# EasyEDA_Schematic_V2_0.net
KiCad netlist of a schematic drawn in EasyEDA
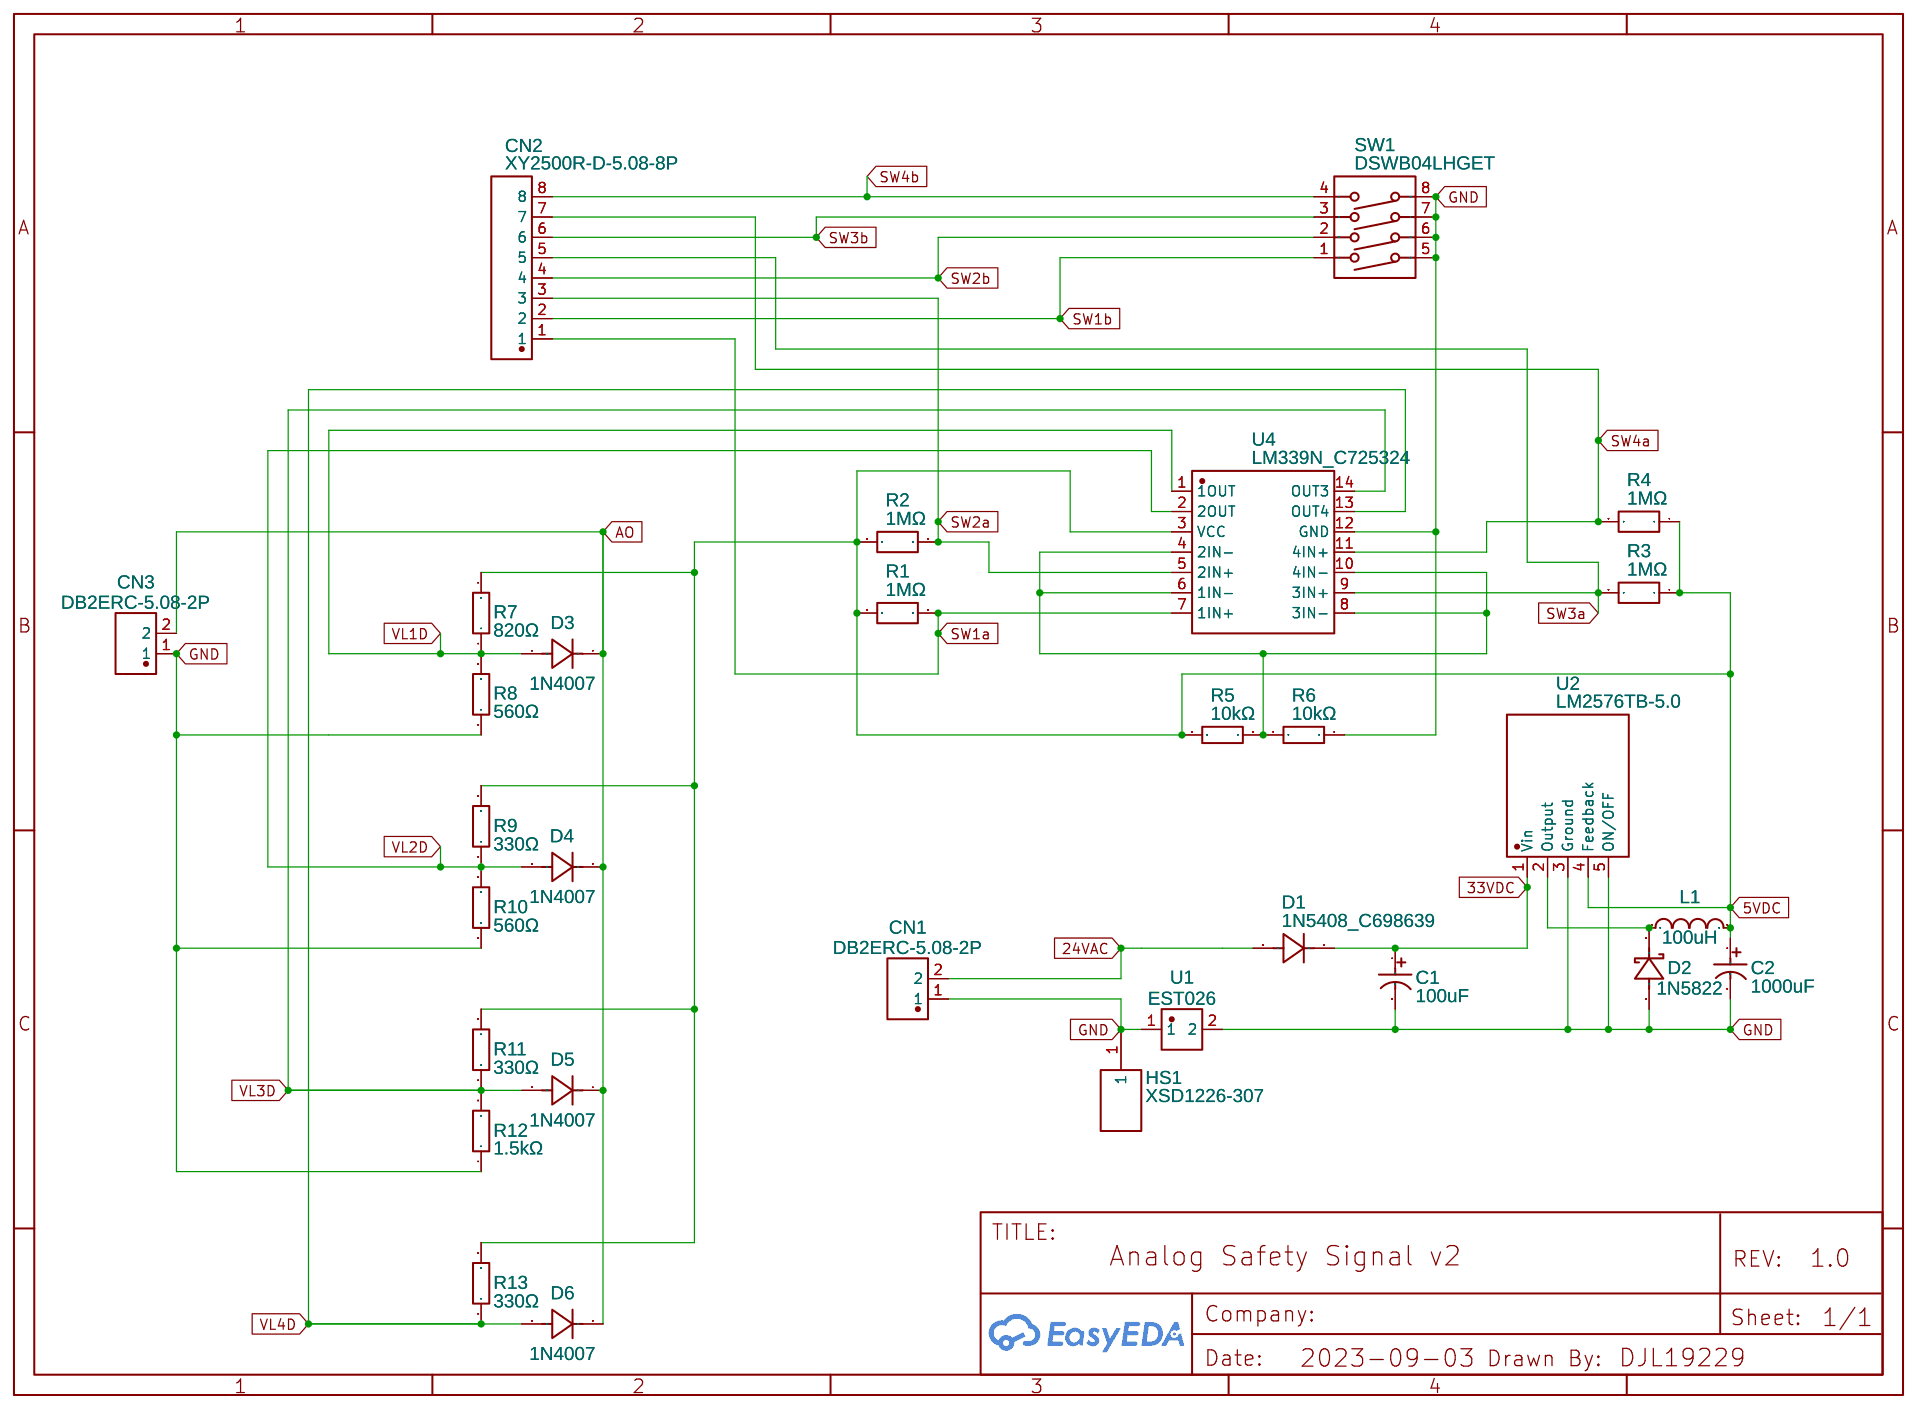
[diagram p0: schematic sheet]

(export (version "E")
  (design (tool "Eeschema 10.0.6"))
  (components
    (comp (ref "C1")
      (value "100uF")
      (fields
        (field (name "Manufacturer Part") "GR107M050F12RR0VH4FP0")
        (field (name "Manufacturer") "CX(承兴)")
      )
      (libsource (lib "") (part "100uF 50V 8*12Black high frequency"))
    )
    (comp (ref "C2")
      (value "1000uF")
      (fields
        (field (name "Manufacturer Part") "35YXJ1000M12.5X20")
        (field (name "Manufacturer") "rubycon(红宝石)")
      )
      (libsource (lib "") (part "35YXJ1000M12.5X20"))
    )
    (comp (ref "CN1")
      (value "DB2ERC-5.08-2P")
      (fields
        (field (name "Manufacturer Part") "DB2ERC-5.08-2P-GN")
        (field (name "Manufacturer") "DIBO(地博电气)")
      )
      (libsource (lib "") (part "DB2ERC-5.08-2P"))
    )
    (comp (ref "CN2")
      (value "XY2500R-D-5.08-8P")
      (fields (field (name "Manufacturer") "XINLAIYA(新莱亚)"))
      (libsource (lib "") (part "XY2500R-D-5.08-8P"))
    )
    (comp (ref "CN3")
      (value "DB2ERC-5.08-2P")
      (fields
        (field (name "Manufacturer Part") "DB2ERC-5.08-2P-GN")
        (field (name "Manufacturer") "DIBO(地博电气)")
      )
      (libsource (lib "") (part "DB2ERC-5.08-2P"))
    )
    (comp (ref "D1")
      (value "1N5408_C698639")
      (fields (field (name "Manufacturer Part") "1N5408") (field (name "Manufacturer") "YANGJIE(扬杰)"))
      (libsource (lib "") (part "1N5408_C698639"))
    )
    (comp (ref "D2")
      (value "1N5822")
      (fields (field (name "Manufacturer") "FUXINSEMI(富芯森美)"))
      (libsource (lib "") (part "1N5822_C3018526"))
    )
    (comp (ref "D3")
      (value "1N4007")
      (fields (field (name "Manufacturer") "YANGJIE(扬杰)"))
      (libsource (lib "") (part "1N4007_C2986225"))
    )
    (comp (ref "D4")
      (value "1N4007")
      (fields (field (name "Manufacturer") "YANGJIE(扬杰)"))
      (libsource (lib "") (part "1N4007_C2986225"))
    )
    (comp (ref "D5")
      (value "1N4007")
      (fields (field (name "Manufacturer") "YANGJIE(扬杰)"))
      (libsource (lib "") (part "1N4007_C2986225"))
    )
    (comp (ref "D6")
      (value "1N4007")
      (fields (field (name "Manufacturer") "YANGJIE(扬杰)"))
      (libsource (lib "") (part "1N4007_C2986225"))
    )
    (comp (ref "HS1")
      (value "XSD1226-307")
      (fields (field (name "Manufacturer") "XSD(鑫顺达)"))
      (libsource (lib "") (part "XSD1226-307"))
    )
    (comp (ref "L1")
      (value "100uH")
      (fields (field (name "Manufacturer Part") "VLU0810-101K") (field (name "Manufacturer") "FH(风华)"))
      (libsource (lib "") (part "VLU0810-101K"))
    )
    (comp (ref "R1")
      (value "1MΩ")
      (fields
        (field (name "Manufacturer Part") "MF1/4W-1MΩ±1%T52")
        (field (name "Manufacturer") "Huaxing Mechanical-Elec.")
      )
      (libsource (lib "") (part "MF1/4W-1MΩ±1%T52"))
    )
    (comp (ref "R2")
      (value "1MΩ")
      (fields
        (field (name "Manufacturer Part") "MF1/4W-1MΩ±1%T52")
        (field (name "Manufacturer") "Huaxing Mechanical-Elec.")
      )
      (libsource (lib "") (part "MF1/4W-1MΩ±1%T52"))
    )
    (comp (ref "R3")
      (value "1MΩ")
      (fields
        (field (name "Manufacturer Part") "MF1/4W-1MΩ±1%T52")
        (field (name "Manufacturer") "Huaxing Mechanical-Elec.")
      )
      (libsource (lib "") (part "MF1/4W-1MΩ±1%T52"))
    )
    (comp (ref "R4")
      (value "1MΩ")
      (fields
        (field (name "Manufacturer Part") "MF1/4W-1MΩ±1%T52")
        (field (name "Manufacturer") "Huaxing Mechanical-Elec.")
      )
      (libsource (lib "") (part "MF1/4W-1MΩ±1%T52"))
    )
    (comp (ref "R5")
      (value "10kΩ")
      (fields (field (name "Manufacturer Part") "MF1/4W-10KΩ±1% T") (field (name "Manufacturer") "CCO(千志电子)"))
      (libsource (lib "") (part "MF1/4W-10KΩ±1% T52"))
    )
    (comp (ref "R6")
      (value "10kΩ")
      (fields (field (name "Manufacturer Part") "MF1/4W-10KΩ±1% T") (field (name "Manufacturer") "CCO(千志电子)"))
      (libsource (lib "") (part "MF1/4W-10KΩ±1% T52"))
    )
    (comp (ref "R7")
      (value "820Ω")
      (fields
        (field (name "Manufacturer Part") "MF1/4W ±1% 820Ω STB5")
        (field (name "Manufacturer") "VO(翔胜)")
      )
      (libsource (lib "") (part "MF1/4W ±1% 820Ω STB5"))
    )
    (comp (ref "R8")
      (value "560Ω")
      (fields (field (name "Manufacturer Part") "MFR-25FTE52-560R") (field (name "Manufacturer") "YAGEO(国巨)"))
      (libsource (lib "") (part "MFR-25FTE52-560R"))
    )
    (comp (ref "R9")
      (value "330Ω")
      (fields (field (name "Manufacturer Part") "MFR-25JT-52-330R") (field (name "Manufacturer") "YAGEO(国巨)"))
      (libsource (lib "") (part "MFR-25JT-52-330R"))
    )
    (comp (ref "R10")
      (value "560Ω")
      (fields (field (name "Manufacturer Part") "MFR-25FTE52-560R") (field (name "Manufacturer") "YAGEO(国巨)"))
      (libsource (lib "") (part "MFR-25FTE52-560R"))
    )
    (comp (ref "R11")
      (value "330Ω")
      (fields (field (name "Manufacturer Part") "MFR-25JT-52-330R") (field (name "Manufacturer") "YAGEO(国巨)"))
      (libsource (lib "") (part "MFR-25JT-52-330R"))
    )
    (comp (ref "R12")
      (value "1.5kΩ")
      (fields
        (field (name "Manufacturer Part") "MF1/4W-1.5KΩ±1% T")
        (field (name "Manufacturer") "CCO(千志电子)")
      )
      (libsource (lib "") (part "MF1/4W-1.5KΩ±1% T52"))
    )
    (comp (ref "R13")
      (value "330Ω")
      (fields (field (name "Manufacturer Part") "MFR-25JT-52-330R") (field (name "Manufacturer") "YAGEO(国巨)"))
      (libsource (lib "") (part "MFR-25JT-52-330R"))
    )
    (comp (ref "SW1")
      (value "DSWB04LHGET")
      (fields (field (name "Manufacturer Part") "拨码开关,平拨开关,DSWB04LHGET") (field (name "Manufacturer") "YE"))
      (libsource (lib "") (part "DSWB04LHGET"))
    )
    (comp (ref "U1")
      (value "EST026")
      (fields (field (name "Manufacturer") "xcfuse(旭程)"))
      (libsource (lib "") (part "EST026"))
    )
    (comp (ref "U2")
      (value "LM2576TB-5.0")
      (fields (field (name "Manufacturer") "HGSEMI(华冠)"))
      (libsource (lib "") (part "LM2576TB-5.0"))
    )
    (comp (ref "U4")
      (value "LM339N_C725324")
      (fields (field (name "Manufacturer Part") "LM339N") (field (name "Manufacturer") "HGSEMI"))
      (libsource (lib "") (part "LM339N_C725324"))
    )
  )
  (nets
    (net (code "1") (name "5VDC") (class "Default")
      (node (ref "C2") (pin "1") (pinfunction "1_1") (pintype "input"))
      (node (ref "L1") (pin "2") (pinfunction "2_2") (pintype "unspecified"))
      (node (ref "R1") (pin "2") (pinfunction "2_2") (pintype "unspecified"))
      (node (ref "R11") (pin "2") (pinfunction "2_2") (pintype "unspecified"))
      (node (ref "R13") (pin "2") (pinfunction "2_2") (pintype "unspecified"))
      (node (ref "R2") (pin "2") (pinfunction "2_2") (pintype "unspecified"))
      (node (ref "R3") (pin "1") (pinfunction "1_1") (pintype "unspecified"))
      (node (ref "R4") (pin "1") (pinfunction "1_1") (pintype "unspecified"))
      (node (ref "R5") (pin "2") (pinfunction "2_2") (pintype "unspecified"))
      (node (ref "R7") (pin "2") (pinfunction "2_2") (pintype "input"))
      (node (ref "R9") (pin "2") (pinfunction "2_2") (pintype "unspecified"))
      (node (ref "U2") (pin "4") (pinfunction "Feedback_4") (pintype "unspecified"))
      (node (ref "U4") (pin "3") (pinfunction "VCC_3") (pintype "unspecified"))
    )
    (net (code "2") (name "24VAC") (class "Default")
      (node (ref "CN1") (pin "2") (pinfunction "2_2") (pintype "unspecified"))
      (node (ref "D1") (pin "2") (pinfunction "A_2") (pintype "unspecified"))
    )
    (net (code "3") (name "33VDC") (class "Default")
      (node (ref "C1") (pin "1") (pinfunction "1_1") (pintype "input"))
      (node (ref "D1") (pin "1") (pinfunction "K_1") (pintype "unspecified"))
      (node (ref "U2") (pin "1") (pinfunction "Vin_1") (pintype "unspecified"))
    )
    (net (code "4") (name "AO") (class "Default")
      (node (ref "CN3") (pin "2") (pinfunction "2_2") (pintype "unspecified"))
      (node (ref "D3") (pin "1") (pinfunction "K_1") (pintype "unspecified"))
      (node (ref "D4") (pin "1") (pinfunction "K_1") (pintype "unspecified"))
      (node (ref "D5") (pin "1") (pinfunction "K_1") (pintype "unspecified"))
      (node (ref "D6") (pin "1") (pinfunction "K_1") (pintype "unspecified"))
    )
    (net (code "5") (name "GND") (class "Default")
      (node (ref "C1") (pin "2") (pinfunction "2_2") (pintype "input"))
      (node (ref "C2") (pin "2") (pinfunction "2_2") (pintype "input"))
      (node (ref "CN1") (pin "1") (pinfunction "1_1") (pintype "unspecified"))
      (node (ref "CN3") (pin "1") (pinfunction "1_1") (pintype "unspecified"))
      (node (ref "D2") (pin "1") (pinfunction "A_1") (pintype "unspecified"))
      (node (ref "HS1") (pin "1") (pinfunction "1_1") (pintype "unspecified"))
      (node (ref "R10") (pin "1") (pinfunction "1_1") (pintype "unspecified"))
      (node (ref "R12") (pin "1") (pinfunction "1_1") (pintype "unspecified"))
      (node (ref "R6") (pin "1") (pinfunction "1_1") (pintype "unspecified"))
      (node (ref "R8") (pin "1") (pinfunction "1_1") (pintype "unspecified"))
      (node (ref "SW1") (pin "5") (pinfunction "5_5") (pintype "unspecified"))
      (node (ref "SW1") (pin "6") (pinfunction "6_6") (pintype "unspecified"))
      (node (ref "SW1") (pin "7") (pinfunction "7_7") (pintype "unspecified"))
      (node (ref "SW1") (pin "8") (pinfunction "8_8") (pintype "unspecified"))
      (node (ref "U1") (pin "1") (pinfunction "1_1") (pintype "unspecified"))
      (node (ref "U1") (pin "2") (pinfunction "2_2") (pintype "unspecified"))
      (node (ref "U2") (pin "3") (pinfunction "Ground_3") (pintype "unspecified"))
      (node (ref "U2") (pin "5") (pinfunction "ON/OFF_5") (pintype "unspecified"))
      (node (ref "U4") (pin "12") (pinfunction "GND_12") (pintype "unspecified"))
    )
    (net (code "6") (name "Net-(D2-K)") (class "Default")
      (node (ref "D2") (pin "2") (pinfunction "K_2") (pintype "unspecified"))
      (node (ref "L1") (pin "1") (pinfunction "1_1") (pintype "unspecified"))
      (node (ref "U2") (pin "2") (pinfunction "Output_2") (pintype "unspecified"))
    )
    (net (code "7") (name "Net-(U4-1IN-)") (class "Default")
      (node (ref "R5") (pin "1") (pinfunction "1_1") (pintype "unspecified"))
      (node (ref "R6") (pin "2") (pinfunction "2_2") (pintype "unspecified"))
      (node (ref "U4") (pin "10") (pinfunction "4IN-_10") (pintype "unspecified"))
      (node (ref "U4") (pin "4") (pinfunction "2IN-_4") (pintype "unspecified"))
      (node (ref "U4") (pin "6") (pinfunction "1IN-_6") (pintype "unspecified"))
      (node (ref "U4") (pin "8") (pinfunction "3IN-_8") (pintype "unspecified"))
    )
    (net (code "8") (name "SW1a") (class "Default")
      (node (ref "CN2") (pin "1") (pinfunction "1_1") (pintype "unspecified"))
      (node (ref "R1") (pin "1") (pinfunction "1_1") (pintype "unspecified"))
      (node (ref "U4") (pin "7") (pinfunction "1IN+_7") (pintype "unspecified"))
    )
    (net (code "9") (name "SW1b") (class "Default")
      (node (ref "CN2") (pin "2") (pinfunction "2_2") (pintype "unspecified"))
      (node (ref "SW1") (pin "1") (pinfunction "1_1") (pintype "unspecified"))
    )
    (net (code "10") (name "SW2a") (class "Default")
      (node (ref "CN2") (pin "3") (pinfunction "3_3") (pintype "unspecified"))
      (node (ref "R2") (pin "1") (pinfunction "1_1") (pintype "unspecified"))
      (node (ref "U4") (pin "5") (pinfunction "2IN+_5") (pintype "unspecified"))
    )
    (net (code "11") (name "SW2b") (class "Default")
      (node (ref "CN2") (pin "4") (pinfunction "4_4") (pintype "unspecified"))
      (node (ref "SW1") (pin "2") (pinfunction "2_2") (pintype "unspecified"))
    )
    (net (code "12") (name "SW3a") (class "Default")
      (node (ref "CN2") (pin "5") (pinfunction "5_5") (pintype "unspecified"))
      (node (ref "R3") (pin "2") (pinfunction "2_2") (pintype "unspecified"))
      (node (ref "U4") (pin "9") (pinfunction "3IN+_9") (pintype "unspecified"))
    )
    (net (code "13") (name "SW3b") (class "Default")
      (node (ref "CN2") (pin "6") (pinfunction "6_6") (pintype "unspecified"))
      (node (ref "SW1") (pin "3") (pinfunction "3_3") (pintype "unspecified"))
    )
    (net (code "14") (name "SW4a") (class "Default")
      (node (ref "CN2") (pin "7") (pinfunction "7_7") (pintype "unspecified"))
      (node (ref "R4") (pin "2") (pinfunction "2_2") (pintype "unspecified"))
      (node (ref "U4") (pin "11") (pinfunction "4IN+_11") (pintype "unspecified"))
    )
    (net (code "15") (name "SW4b") (class "Default")
      (node (ref "CN2") (pin "8") (pinfunction "8_8") (pintype "unspecified"))
      (node (ref "SW1") (pin "4") (pinfunction "4_4") (pintype "unspecified"))
    )
    (net (code "16") (name "VL1D") (class "Default")
      (node (ref "D3") (pin "2") (pinfunction "A_2") (pintype "unspecified"))
      (node (ref "R7") (pin "1") (pinfunction "1_1") (pintype "input"))
      (node (ref "R8") (pin "2") (pinfunction "2_2") (pintype "unspecified"))
      (node (ref "U4") (pin "1") (pinfunction "1OUT_1") (pintype "unspecified"))
    )
    (net (code "17") (name "VL2D") (class "Default")
      (node (ref "D4") (pin "2") (pinfunction "A_2") (pintype "unspecified"))
      (node (ref "R10") (pin "2") (pinfunction "2_2") (pintype "unspecified"))
      (node (ref "R9") (pin "1") (pinfunction "1_1") (pintype "unspecified"))
      (node (ref "U4") (pin "2") (pinfunction "2OUT_2") (pintype "unspecified"))
    )
    (net (code "18") (name "VL3D") (class "Default")
      (node (ref "D5") (pin "2") (pinfunction "A_2") (pintype "unspecified"))
      (node (ref "R11") (pin "1") (pinfunction "1_1") (pintype "unspecified"))
      (node (ref "R12") (pin "2") (pinfunction "2_2") (pintype "unspecified"))
      (node (ref "U4") (pin "14") (pinfunction "OUT3_14") (pintype "unspecified"))
    )
    (net (code "19") (name "VL4D") (class "Default")
      (node (ref "D6") (pin "2") (pinfunction "A_2") (pintype "unspecified"))
      (node (ref "R13") (pin "1") (pinfunction "1_1") (pintype "unspecified"))
      (node (ref "U4") (pin "13") (pinfunction "OUT4_13") (pintype "unspecified"))
    )
  )
)
